# Power_Regulators_Digital_5.net
KiCad netlist of a schematic drawn in Altium Designer
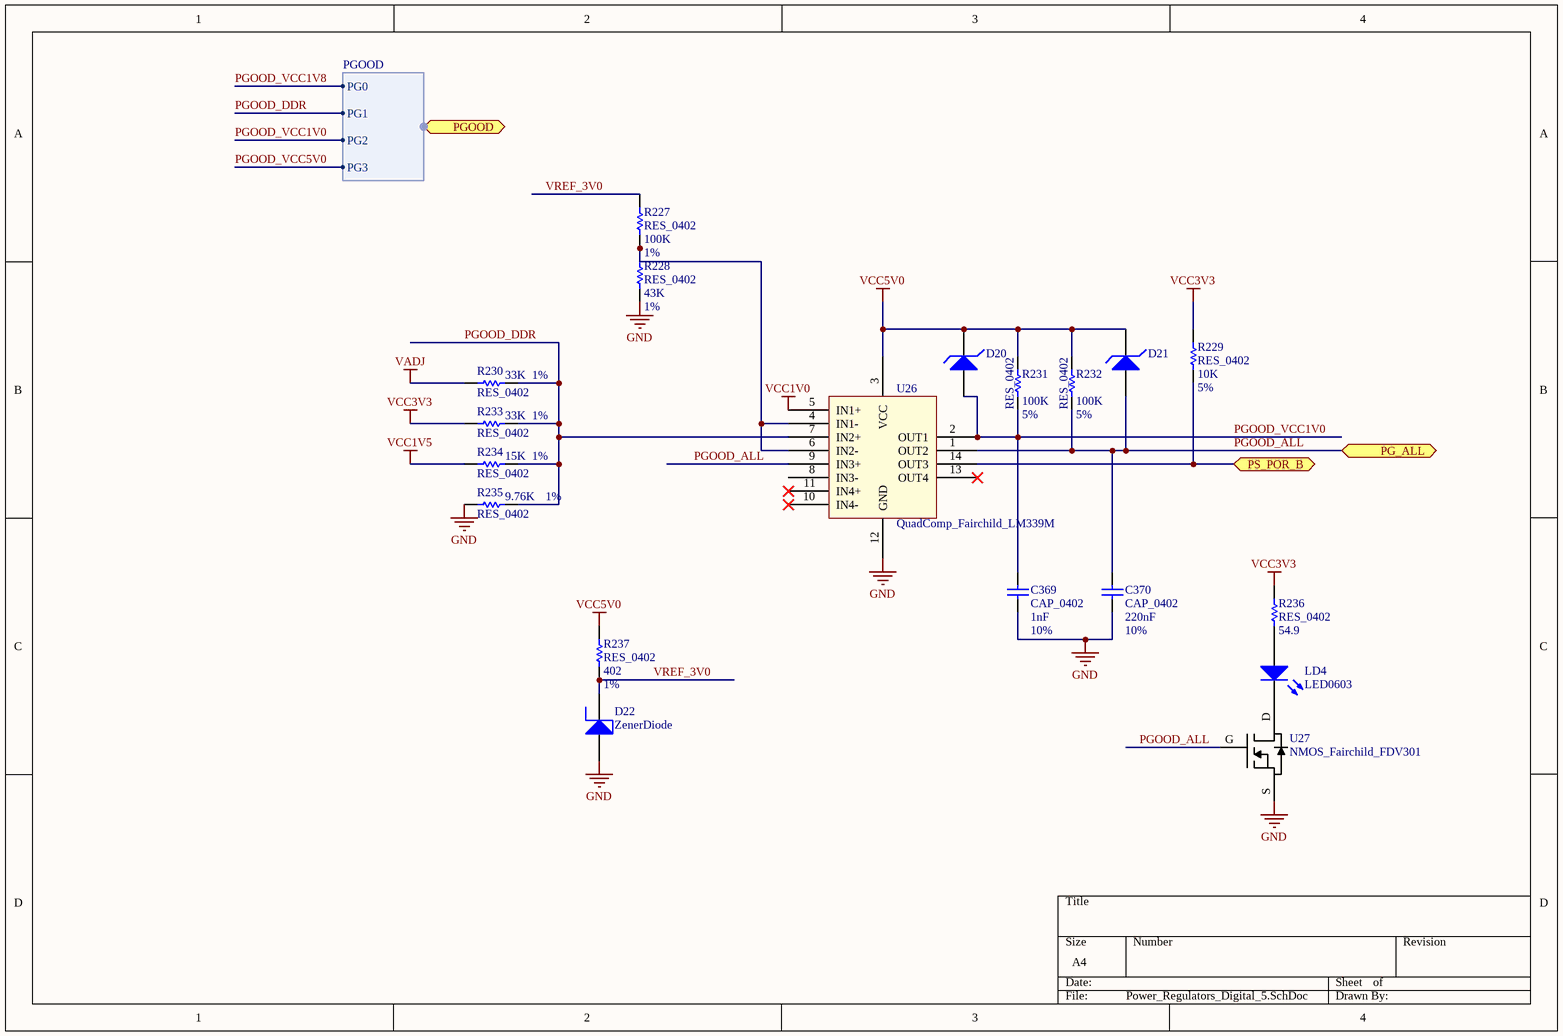
[diagram p0: Power_Regulators_Digital_5.SchDoc]

(export (version "E")
  (design (tool "Eeschema 10.0.6"))
  (components
    (comp (ref "C369")
      (value "CAP_0402")
      (footprint "CAPC0402(1005)60_N")
      (description "1000pF, ceramic, 10% 25V X7R, 0402")
      (fields
        (field (name "ALTIUM_VALUE") "1nF")
        (field (name "TOLERANCE") "10%")
        (field (name "PART NUMBER") "ECJ-0EB1E102K")
        (field (name "MANUFACTURER") "Panasonic - ECG")
      )
      (libsource (lib "COMRAD_Database") (part "CAP_0402"))
    )
    (comp (ref "C370")
      (value "CAP_0402")
      (footprint "CAPC0402(1005)60_N")
      (description "0.22uF, ceramic, 10% 10V X5R, 0402")
      (fields
        (field (name "ALTIUM_VALUE") "220nF")
        (field (name "TOLERANCE") "10%")
        (field (name "PART NUMBER") "LMK105BJ224KV-F")
        (field (name "MANUFACTURER") "Taiyo Yuden")
      )
      (libsource (lib "COMRAD_Database") (part "CAP_0402"))
    )
    (comp (ref "D20")
      (value "Shottky Diode")
      (footprint "SchottkyDiode_RB751S40_2-PIN")
      (description "RB751S40, 40V 30mA schottky, SOD523F")
      (fields (field (name "PART NUMBER") "RB751S40") (field (name "MANUFACTURER") "FAIRCHILD SEMICONDUCTOR"))
      (libsource (lib "COMRAD_Database") (part "ShottkyDiode"))
    )
    (comp (ref "D21")
      (value "Shottky Diode")
      (footprint "SchottkyDiode_RB751S40_2-PIN")
      (description "RB751S40, 40V 30mA schottky, SOD523F")
      (fields (field (name "PART NUMBER") "RB751S40") (field (name "MANUFACTURER") "FAIRCHILD SEMICONDUCTOR"))
      (libsource (lib "COMRAD_Database") (part "ShottkyDiode"))
    )
    (comp (ref "D22")
      (value "ZenerDiode")
      (footprint "ZenerDiode_BZX84-A3V0215_SOT23-3")
      (description "BZX84-A3V0, VReg 250mW 3V, SOT23")
      (fields
        (field (name "PART NUMBER") "BZX84-A3V0,215")
        (field (name "MANUFACTURER") "NXP Semiconductors")
      )
      (libsource (lib "COMRAD_Database") (part "ZenerDiode_BZX84-A3V0"))
    )
    (comp (ref "LD4")
      (value "LED0603")
      (footprint "LED0603(1608)_HSMG-C190")
      (description "LED 570NM GREEN DIFF 0603 SMD")
      (fields (field (name "PART NUMBER") "\"HSMG-C190\"") (field (name "MANUFACTURER") "Avago"))
      (libsource (lib "COMRAD_Database") (part "LED0603"))
    )
    (comp (ref "R227")
      (value "RES_0402")
      (footprint "RESC0402(1005)_N")
      (description "100K ohm, 1%, 1/16W, 0402")
      (fields
        (field (name "ALTIUM_VALUE") "100K")
        (field (name "TOLERANCE") "1%")
        (field (name "PART NUMBER") "MCR01MZPF1003")
        (field (name "MANUFACTURER") "ROHM")
      )
      (libsource (lib "COMRAD_Database") (part "RES_0402"))
    )
    (comp (ref "R228")
      (value "RES_0402")
      (footprint "RESC0402(1005)_N")
      (description "43K ohm, 1% 1/10W, 0402")
      (fields
        (field (name "ALTIUM_VALUE") "43K")
        (field (name "TOLERANCE") "1%")
        (field (name "PART NUMBER") "ERJ-2RKF4302X")
        (field (name "MANUFACTURER") "Panasonic - ECG")
      )
      (libsource (lib "COMRAD_Database") (part "RES_0402"))
    )
    (comp (ref "R229")
      (value "RES_0402")
      (footprint "RESC0402(1005)_N")
      (description "10K ohm, 5%, 1/16W, 0402")
      (fields
        (field (name "ALTIUM_VALUE") "10K")
        (field (name "TOLERANCE") "5%")
        (field (name "PART NUMBER") "RC0402JR-0710KL")
        (field (name "MANUFACTURER") "Yageo America")
      )
      (libsource (lib "COMRAD_Database") (part "RES_0402"))
    )
    (comp (ref "R230")
      (value "RES_0402")
      (footprint "RESC0402(1005)_N")
      (description "33K ohms, 1% 1/16W, 0402")
      (fields
        (field (name "ALTIUM_VALUE") "33K")
        (field (name "TOLERANCE") "1%")
        (field (name "PART NUMBER") "RK73H1ETTP3302F")
        (field (name "MANUFACTURER") "KOA Speer Electronics")
      )
      (libsource (lib "COMRAD_Database") (part "RES_0402"))
    )
    (comp (ref "R231")
      (value "RES_0402")
      (footprint "RESC0402(1005)_N")
      (description "100K ohm, 5%, 1/16W, 0402")
      (fields
        (field (name "ALTIUM_VALUE") "100K")
        (field (name "TOLERANCE") "5%")
        (field (name "PART NUMBER") "RC0402JR-07100KL")
        (field (name "MANUFACTURER") "Yageo America")
      )
      (libsource (lib "COMRAD_Database") (part "RES_0402"))
    )
    (comp (ref "R232")
      (value "RES_0402")
      (footprint "RESC0402(1005)_N")
      (description "100K ohm, 5%, 1/16W, 0402")
      (fields
        (field (name "ALTIUM_VALUE") "100K")
        (field (name "TOLERANCE") "5%")
        (field (name "PART NUMBER") "RC0402JR-07100KL")
        (field (name "MANUFACTURER") "Yageo America")
      )
      (libsource (lib "COMRAD_Database") (part "RES_0402"))
    )
    (comp (ref "R233")
      (value "RES_0402")
      (footprint "RESC0402(1005)_N")
      (description "33K ohms, 1% 1/16W, 0402")
      (fields
        (field (name "ALTIUM_VALUE") "33K")
        (field (name "TOLERANCE") "1%")
        (field (name "PART NUMBER") "RK73H1ETTP3302F")
        (field (name "MANUFACTURER") "KOA Speer Electronics")
      )
      (libsource (lib "COMRAD_Database") (part "RES_0402"))
    )
    (comp (ref "R234")
      (value "RES_0402")
      (footprint "RESC0402(1005)_N")
      (description "15K ohm, 1% 1/10W, 0402")
      (fields
        (field (name "ALTIUM_VALUE") "15K")
        (field (name "TOLERANCE") "1%")
        (field (name "PART NUMBER") "ERJ-2RKF1502X")
        (field (name "MANUFACTURER") "Panasonic - ECG")
      )
      (libsource (lib "COMRAD_Database") (part "RES_0402"))
    )
    (comp (ref "R235")
      (value "RES_0402")
      (footprint "RESC0402(1005)_N")
      (description "9.76K ohm, 1% 1/16W, 0402")
      (fields
        (field (name "ALTIUM_VALUE") "9.76K")
        (field (name "TOLERANCE") "1%")
        (field (name "PART NUMBER") "CRCW04029K76FKED")
        (field (name "MANUFACTURER") "Vishay/Dale")
      )
      (libsource (lib "COMRAD_Database") (part "RES_0402"))
    )
    (comp (ref "R236")
      (value "RES_0402")
      (footprint "RESC0402(1005)_N")
      (description "RES 54.9 OHM 1/10W 1% 0402 SMD")
      (fields
        (field (name "ALTIUM_VALUE") "54.9")
        (field (name "PART NUMBER") "ERJ-2RKF54R9X")
        (field (name "MANUFACTURER") "Panasonic Electronic Components")
      )
      (libsource (lib "COMRAD_Database") (part "RES_0402"))
    )
    (comp (ref "R237")
      (value "RES_0402")
      (footprint "RESC0402(1005)_N")
      (description "402 ohm, 1%, 1/16W, 0402")
      (fields
        (field (name "ALTIUM_VALUE") "402")
        (field (name "TOLERANCE") "1%")
        (field (name "PART NUMBER") "CRCW0402402RFKED")
        (field (name "MANUFACTURER") "Vishay/Dale")
      )
      (libsource (lib "COMRAD_Database") (part "RES_0402"))
    )
    (comp (ref "U26")
      (value "QuadComp_Fairchild_LM339M")
      (footprint "QuadComp_Fairchild_LM339MX-NOPB_14SOIC")
      (description "Quad Comparator,14-SOP")
      (fields (field (name "PART NUMBER") "LM339MX/NOPB") (field (name "MANUFACTURER") "Fairchild"))
      (libsource (lib "COMRAD_Database") (part "QuadComp_Fairchild_LM339M"))
    )
    (comp (ref "U27")
      (value "NMOS_Fairchild_FDV301")
      (footprint "NMOS_Fairchild_FDV301_SOT23-3")
      (description "MOSFET N-CH 25V 220MA SOT-23")
      (fields (field (name "PART NUMBER") "FDV301N") (field (name "MANUFACTURER") "Fairchild Semiconductor"))
      (libsource (lib "COMRAD_Database") (part "NMOS_Fairchild_FDV301"))
    )
  )
  (nets
    (net (code "2") (name "/PGOOD_ALL") (class "Default")
      (node (ref "C370") (pin "2") (pinfunction "2_2") (pintype "passive"))
      (node (ref "D21") (pin "2") (pinfunction "A_2") (pintype "passive"))
      (node (ref "R232") (pin "1") (pinfunction "1_1") (pintype "passive"))
      (node (ref "U26") (pin "1") (pinfunction "OUT2_1") (pintype "passive"))
      (node (ref "U26") (pin "9") (pinfunction "IN3+_9") (pintype "passive"))
      (node (ref "U27") (pin "G") (pintype "passive"))
    )
    (net (code "3") (name "/PGOOD_DDR") (class "Default")
      (node (ref "R230") (pin "2") (pinfunction "2_2") (pintype "passive"))
      (node (ref "R233") (pin "2") (pinfunction "2_2") (pintype "passive"))
      (node (ref "R234") (pin "2") (pinfunction "2_2") (pintype "passive"))
      (node (ref "R235") (pin "2") (pinfunction "2_2") (pintype "passive"))
      (node (ref "U26") (pin "7") (pinfunction "IN2+_7") (pintype "passive"))
    )
    (net (code "4") (name "/PGOOD_VCC1V0") (class "Default")
      (node (ref "C369") (pin "2") (pinfunction "2_2") (pintype "passive"))
      (node (ref "D20") (pin "2") (pinfunction "A_2") (pintype "passive"))
      (node (ref "R231") (pin "1") (pinfunction "1_1") (pintype "passive"))
      (node (ref "U26") (pin "2") (pinfunction "OUT1_2") (pintype "passive"))
    )
    (net (code "7") (name "/PS_POR_B") (class "Default")
      (node (ref "R229") (pin "1") (pinfunction "1_1") (pintype "passive"))
      (node (ref "U26") (pin "14") (pinfunction "OUT3_14") (pintype "passive"))
    )
    (net (code "8") (name "/VREF_3V0") (class "Default")
      (node (ref "D22") (pin "3") (pinfunction "K_3") (pintype "passive"))
      (node (ref "R227") (pin "2") (pinfunction "2_2") (pintype "passive"))
      (node (ref "R237") (pin "1") (pinfunction "1_1") (pintype "passive"))
    )
    (net (code "10") (name "GND") (class "Default")
      (node (ref "C369") (pin "1") (pinfunction "1_1") (pintype "passive"))
      (node (ref "C370") (pin "1") (pinfunction "1_1") (pintype "passive"))
      (node (ref "D22") (pin "1") (pinfunction "A_1") (pintype "passive"))
      (node (ref "R228") (pin "1") (pinfunction "1_1") (pintype "passive"))
      (node (ref "R235") (pin "1") (pinfunction "1_1") (pintype "passive"))
      (node (ref "U26") (pin "12") (pinfunction "GND_12") (pintype "passive"))
      (node (ref "U27") (pin "S") (pintype "passive"))
    )
    (net (code "11") (name "Net-(LD4-A)") (class "Default")
      (node (ref "LD4") (pin "2") (pinfunction "A_2") (pintype "passive"))
      (node (ref "R236") (pin "1") (pinfunction "1_1") (pintype "passive"))
    )
    (net (code "12") (name "Net-(LD4-K)") (class "Default")
      (node (ref "LD4") (pin "1") (pinfunction "K_1") (pintype "passive"))
      (node (ref "U27") (pin "D") (pintype "passive"))
    )
    (net (code "13") (name "Net-(U26-IN1-)") (class "Default")
      (node (ref "R227") (pin "1") (pinfunction "1_1") (pintype "passive"))
      (node (ref "R228") (pin "2") (pinfunction "2_2") (pintype "passive"))
      (node (ref "U26") (pin "4") (pinfunction "IN1-_4") (pintype "passive"))
      (node (ref "U26") (pin "6") (pinfunction "IN2-_6") (pintype "passive"))
    )
    (net (code "14") (name "VADJ") (class "Default")
      (node (ref "R230") (pin "1") (pinfunction "1_1") (pintype "passive"))
    )
    (net (code "15") (name "VCC1V0") (class "Default")
      (node (ref "U26") (pin "5") (pinfunction "IN1+_5") (pintype "passive"))
    )
    (net (code "16") (name "VCC1V5") (class "Default")
      (node (ref "R234") (pin "1") (pinfunction "1_1") (pintype "passive"))
    )
    (net (code "17") (name "VCC3V3") (class "Default")
      (node (ref "R229") (pin "2") (pinfunction "2_2") (pintype "passive"))
      (node (ref "R233") (pin "1") (pinfunction "1_1") (pintype "passive"))
      (node (ref "R236") (pin "2") (pinfunction "2_2") (pintype "passive"))
    )
    (net (code "18") (name "VCC5V0") (class "Default")
      (node (ref "D20") (pin "1") (pinfunction "K_1") (pintype "passive"))
      (node (ref "D21") (pin "1") (pinfunction "K_1") (pintype "passive"))
      (node (ref "R231") (pin "2") (pinfunction "2_2") (pintype "passive"))
      (node (ref "R232") (pin "2") (pinfunction "2_2") (pintype "passive"))
      (node (ref "R237") (pin "2") (pinfunction "2_2") (pintype "passive"))
      (node (ref "U26") (pin "3") (pinfunction "VCC_3") (pintype "passive"))
    )
    (net (code "19") (name "unconnected-(U26-IN3--Pad8)") (class "Default")
      (node (ref "U26") (pin "8") (pinfunction "IN3-_8") (pintype "passive"))
    )
    (net (code "20") (name "unconnected-(U26-IN4+-Pad11)") (class "Default")
      (node (ref "U26") (pin "11") (pinfunction "IN4+_11") (pintype "passive+no_connect"))
    )
    (net (code "21") (name "unconnected-(U26-IN4--Pad10)") (class "Default")
      (node (ref "U26") (pin "10") (pinfunction "IN4-_10") (pintype "passive+no_connect"))
    )
    (net (code "22") (name "unconnected-(U26-OUT4-Pad13)") (class "Default")
      (node (ref "U26") (pin "13") (pinfunction "OUT4_13") (pintype "passive+no_connect"))
    )
  )
)
